# GSM.net
KiCad netlist of a schematic drawn in Altium Designer
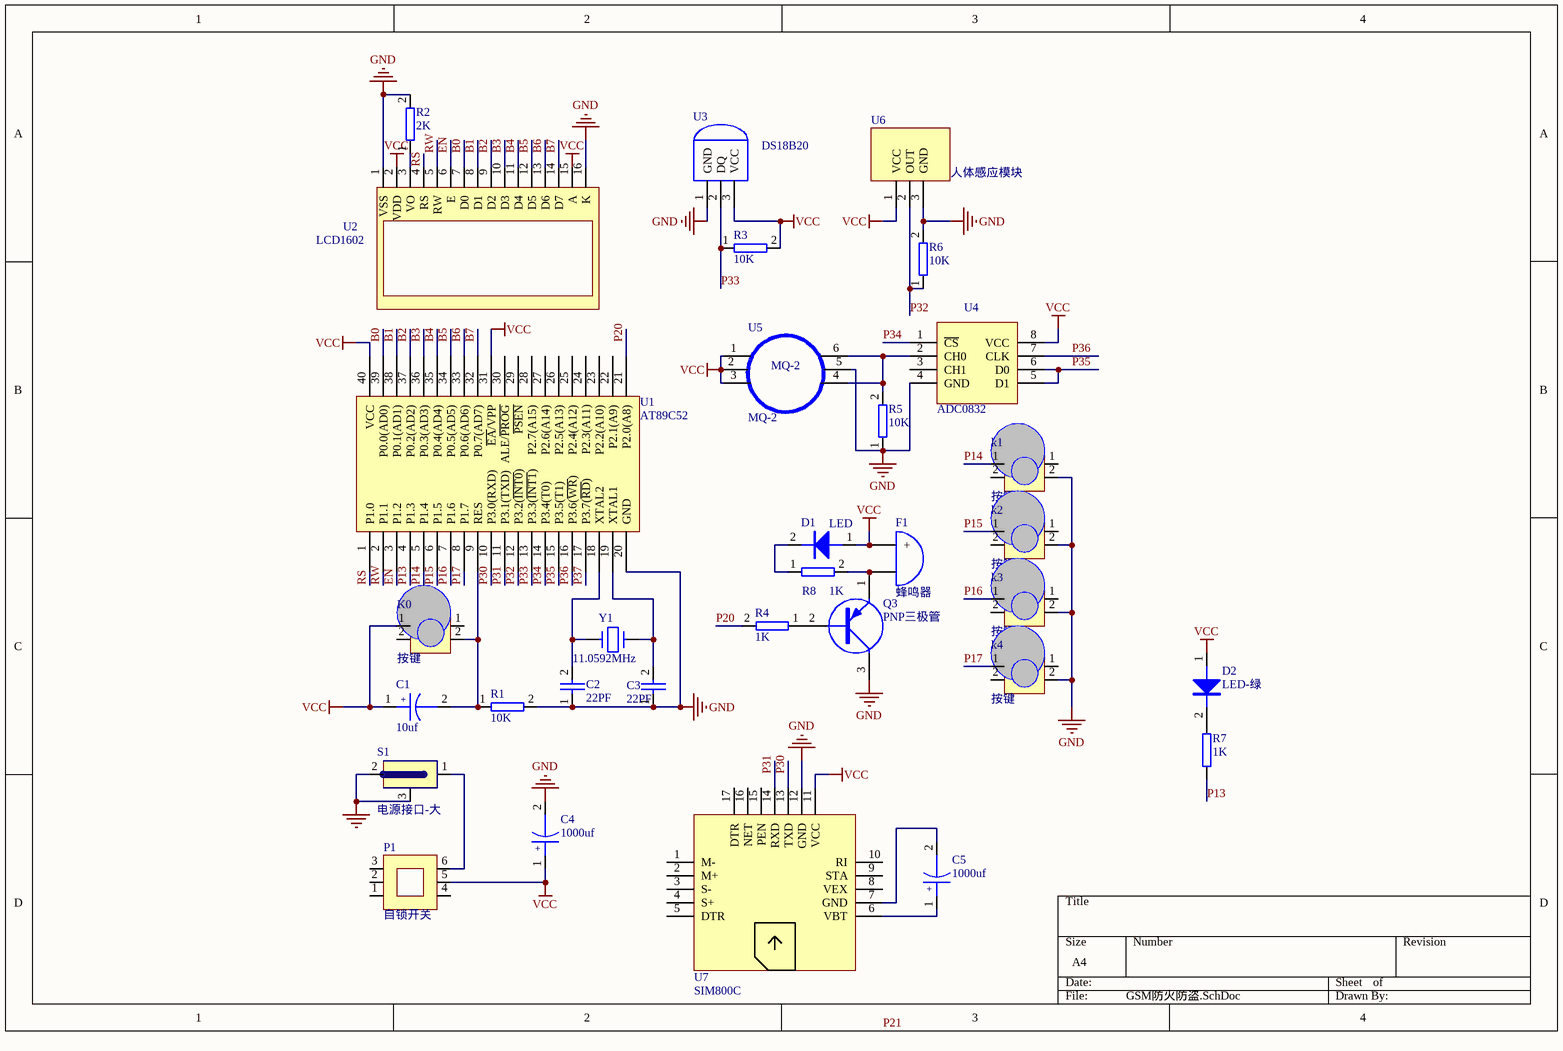
[diagram p0: GSM防火防盗.SchDoc]

(export (version "E")
  (design (tool "Eeschema 10.0.6"))
  (components
    (comp (ref "C1") (value "10uf") (footprint "电容-电解10UF") (libsource (lib "元件集成库") (part "电解电容")))
    (comp (ref "C2") (value "22PF") (footprint "电容-瓷片") (libsource (lib "元件集成库") (part "瓷片电容")))
    (comp (ref "C3") (value "22PF") (footprint "电容-瓷片") (libsource (lib "元件集成库") (part "瓷片电容")))
    (comp (ref "C4")
      (value "1000uf")
      (footprint "电容-电解1000UF - 25V")
      (libsource (lib "元件集成库") (part "电解电容-1000uf-25v"))
    )
    (comp (ref "C5")
      (value "1000uf")
      (footprint "电容-电解1000UF - 25V")
      (libsource (lib "元件集成库") (part "电解电容-1000uf-25v"))
    )
    (comp (ref "D1") (value "LED") (footprint "LED") (libsource (lib "元件集成库") (part "LED")))
    (comp (ref "D2") (value "LED-绿") (footprint "LED-5MM") (libsource (lib "元件集成库") (part "LED-5MM")))
    (comp (ref "F1") (value "蜂鸣器") (footprint "蜂鸣器") (libsource (lib "元件集成库") (part "蜂鸣器")))
    (comp (ref "K0") (value "按键") (footprint "按键") (libsource (lib "元件集成库") (part "按键")))
    (comp (ref "k1") (value "按键") (footprint "按键") (libsource (lib "元件集成库") (part "按键")))
    (comp (ref "k2") (value "按键") (footprint "按键") (libsource (lib "元件集成库") (part "按键")))
    (comp (ref "k3") (value "按键") (footprint "按键") (libsource (lib "元件集成库") (part "按键")))
    (comp (ref "k4") (value "按键") (footprint "按键") (libsource (lib "元件集成库") (part "按键")))
    (comp (ref "P1") (value "自锁开关") (footprint "自锁开关") (libsource (lib "元件集成库") (part "自锁开关")))
    (comp (ref "Q3") (value "PNP三极管") (footprint "三极管") (libsource (lib "元件集成库") (part "PNP三极管")))
    (comp (ref "R1") (value "10K") (footprint "电阻") (libsource (lib "元件集成库") (part "电阻-定值")))
    (comp (ref "R2") (value "2K") (footprint "电阻") (libsource (lib "元件集成库") (part "电阻-定值")))
    (comp (ref "R3") (value "10K") (footprint "电阻") (libsource (lib "元件集成库") (part "电阻-定值")))
    (comp (ref "R4") (value "1K") (footprint "电阻") (libsource (lib "元件集成库") (part "电阻-定值")))
    (comp (ref "R5") (value "10K") (footprint "电阻") (libsource (lib "元件集成库") (part "电阻-定值")))
    (comp (ref "R6") (value "10K") (footprint "电阻") (libsource (lib "元件集成库") (part "电阻-定值")))
    (comp (ref "R7") (value "1K") (footprint "电阻") (libsource (lib "") (part "电阻-定值_1")))
    (comp (ref "R8") (value "1K") (footprint "电阻") (libsource (lib "元件集成库") (part "电阻-定值")))
    (comp (ref "S1") (value "电源接口-大") (footprint "电源座-大") (libsource (lib "元件集成库") (part "电源接口-大")))
    (comp (ref "U1") (value "AT89C52") (footprint "底座40P") (libsource (lib "元件集成库") (part "STC89C52")))
    (comp (ref "U2") (value "LCD1602") (footprint "LCD1602") (libsource (lib "元件集成库") (part "LCD1602")))
    (comp (ref "U3") (value "DS18B20") (footprint "三极管") (libsource (lib "元件集成库") (part "DS18B20")))
    (comp (ref "U4") (value "ADC0832") (footprint "底座8P") (libsource (lib "元件集成库") (part "ADC0832")))
    (comp (ref "U5") (value "MQ-2") (footprint "MQ-2") (libsource (lib "元件集成库") (part "MQ-2")))
    (comp (ref "U6") (value "人体感应模块") (footprint "人体感应模块") (libsource (lib "元件集成库") (part "人体感应模块")))
    (comp (ref "U7") (value "SIM800C") (footprint "SIM800C") (libsource (lib "元件集成库") (part "SIM800C")))
    (comp (ref "Y1") (value "11.0592MHz") (footprint "晶振") (libsource (lib "元件集成库") (part "晶振")))
  )
  (nets
    (net (code "1") (name "/B0") (class "Default")
      (node (ref "U1") (pin "39") (pinfunction "P0.0(AD0)_39") (pintype "passive"))
      (node (ref "U2") (pin "7") (pinfunction "D0_7") (pintype "passive"))
    )
    (net (code "2") (name "/B1") (class "Default")
      (node (ref "U1") (pin "38") (pinfunction "P0.1(AD1)_38") (pintype "passive"))
      (node (ref "U2") (pin "8") (pinfunction "D1_8") (pintype "passive"))
    )
    (net (code "3") (name "/B2") (class "Default")
      (node (ref "U1") (pin "37") (pinfunction "P0.2(AD2)_37") (pintype "passive"))
      (node (ref "U2") (pin "9") (pinfunction "D2_9") (pintype "passive"))
    )
    (net (code "4") (name "/B3") (class "Default")
      (node (ref "U1") (pin "36") (pinfunction "P0.3(AD3)_36") (pintype "passive"))
      (node (ref "U2") (pin "10") (pinfunction "D3_10") (pintype "passive"))
    )
    (net (code "5") (name "/B4") (class "Default")
      (node (ref "U1") (pin "35") (pinfunction "P0.4(AD4)_35") (pintype "passive"))
      (node (ref "U2") (pin "11") (pinfunction "D4_11") (pintype "passive"))
    )
    (net (code "6") (name "/B5") (class "Default")
      (node (ref "U1") (pin "34") (pinfunction "P0.5(AD5)_34") (pintype "passive"))
      (node (ref "U2") (pin "12") (pinfunction "D5_12") (pintype "passive"))
    )
    (net (code "7") (name "/B6") (class "Default")
      (node (ref "U1") (pin "33") (pinfunction "P0.6(AD6)_33") (pintype "passive"))
      (node (ref "U2") (pin "13") (pinfunction "D6_13") (pintype "passive"))
    )
    (net (code "8") (name "/B7") (class "Default")
      (node (ref "U1") (pin "32") (pinfunction "P0.7(AD7)_32") (pintype "passive"))
      (node (ref "U2") (pin "14") (pinfunction "D7_14") (pintype "passive"))
    )
    (net (code "9") (name "/EN") (class "Default")
      (node (ref "U1") (pin "3") (pinfunction "P1.2_3") (pintype "passive"))
      (node (ref "U2") (pin "6") (pinfunction "E_6") (pintype "passive"))
    )
    (net (code "10") (name "/P13") (class "Default")
      (node (ref "R7") (pin "1") (pinfunction "1_1") (pintype "passive"))
      (node (ref "U1") (pin "4") (pinfunction "P1.3_4") (pintype "passive"))
    )
    (net (code "11") (name "/P14") (class "Default")
      (node (ref "U1") (pin "5") (pinfunction "P1.4_5") (pintype "passive"))
      (node (ref "k1") (pin "1") (pinfunction "1_1") (pintype "passive"))
    )
    (net (code "12") (name "/P15") (class "Default")
      (node (ref "U1") (pin "6") (pinfunction "P1.5_6") (pintype "passive"))
      (node (ref "k2") (pin "1") (pinfunction "1_1") (pintype "passive"))
    )
    (net (code "13") (name "/P16") (class "Default")
      (node (ref "U1") (pin "7") (pinfunction "P1.6_7") (pintype "passive"))
      (node (ref "k3") (pin "1") (pinfunction "1_1") (pintype "passive"))
    )
    (net (code "14") (name "/P17") (class "Default")
      (node (ref "U1") (pin "8") (pinfunction "P1.7_8") (pintype "passive"))
      (node (ref "k4") (pin "1") (pinfunction "1_1") (pintype "passive"))
    )
    (net (code "15") (name "/P20") (class "Default")
      (node (ref "R4") (pin "2") (pinfunction "2_2") (pintype "passive"))
      (node (ref "U1") (pin "21") (pinfunction "P2.0(A8)_21") (pintype "passive"))
    )
    (net (code "17") (name "/P30") (class "Default")
      (node (ref "U1") (pin "10") (pinfunction "P3.0(RXD)_10") (pintype "passive"))
      (node (ref "U7") (pin "13") (pinfunction "TXD_13") (pintype "passive"))
    )
    (net (code "18") (name "/P31") (class "Default")
      (node (ref "U1") (pin "11") (pinfunction "P3.1(TXD)_11") (pintype "passive"))
      (node (ref "U7") (pin "14") (pinfunction "RXD_14") (pintype "passive"))
    )
    (net (code "19") (name "/P32") (class "Default")
      (node (ref "R6") (pin "1") (pinfunction "1_1") (pintype "passive"))
      (node (ref "U1") (pin "12") (pinfunction "P3.2(~{INT0})_12") (pintype "passive"))
      (node (ref "U6") (pin "2") (pinfunction "OUT_2") (pintype "passive"))
    )
    (net (code "20") (name "/P33") (class "Default")
      (node (ref "R3") (pin "1") (pinfunction "1_1") (pintype "passive"))
      (node (ref "U1") (pin "13") (pinfunction "P3.3(~{INT1})_13") (pintype "passive"))
      (node (ref "U3") (pin "2") (pinfunction "DQ_2") (pintype "passive"))
    )
    (net (code "21") (name "/P34") (class "Default")
      (node (ref "U1") (pin "14") (pinfunction "P3.4(T0)_14") (pintype "passive"))
      (node (ref "U4") (pin "1") (pinfunction "~{CS}_1") (pintype "passive"))
    )
    (net (code "22") (name "/P35") (class "Default")
      (node (ref "U1") (pin "15") (pinfunction "P3.5(T1)_15") (pintype "passive"))
      (node (ref "U4") (pin "5") (pinfunction "D1_5") (pintype "passive"))
      (node (ref "U4") (pin "6") (pinfunction "D0_6") (pintype "passive"))
    )
    (net (code "23") (name "/P36") (class "Default")
      (node (ref "U1") (pin "16") (pinfunction "P3.6(~{WR})_16") (pintype "passive"))
      (node (ref "U4") (pin "7") (pinfunction "CLK_7") (pintype "passive"))
    )
    (net (code "24") (name "/P37") (class "Default")
      (node (ref "U1") (pin "17") (pinfunction "P3.7(~{RD})_17") (pintype "passive"))
    )
    (net (code "25") (name "/RS") (class "Default")
      (node (ref "U1") (pin "1") (pinfunction "P1.0_1") (pintype "passive"))
      (node (ref "U2") (pin "4") (pinfunction "RS_4") (pintype "passive"))
    )
    (net (code "26") (name "/RW") (class "Default")
      (node (ref "U1") (pin "2") (pinfunction "P1.1_2") (pintype "passive"))
      (node (ref "U2") (pin "5") (pinfunction "RW_5") (pintype "passive"))
    )
    (net (code "27") (name "GND") (class "Default")
      (node (ref "C2") (pin "1") (pinfunction "1_1") (pintype "passive"))
      (node (ref "C3") (pin "1") (pinfunction "1_1") (pintype "passive"))
      (node (ref "C4") (pin "2") (pinfunction "2_2") (pintype "passive"))
      (node (ref "Q3") (pin "3") (pinfunction "C_3") (pintype "passive"))
      (node (ref "R1") (pin "2") (pinfunction "2_2") (pintype "passive"))
      (node (ref "R2") (pin "2") (pinfunction "2_2") (pintype "passive"))
      (node (ref "R5") (pin "1") (pinfunction "1_1") (pintype "passive"))
      (node (ref "R6") (pin "2") (pinfunction "2_2") (pintype "passive"))
      (node (ref "S1") (pin "2") (pinfunction "2_2") (pintype "passive"))
      (node (ref "S1") (pin "3") (pinfunction "3_3") (pintype "passive"))
      (node (ref "U1") (pin "20") (pinfunction "GND_20") (pintype "passive"))
      (node (ref "U2") (pin "1") (pinfunction "VSS_1") (pintype "passive"))
      (node (ref "U2") (pin "16") (pinfunction "K_16") (pintype "passive"))
      (node (ref "U3") (pin "1") (pinfunction "GND_1") (pintype "passive"))
      (node (ref "U4") (pin "4") (pinfunction "GND_4") (pintype "passive"))
      (node (ref "U5") (pin "5") (pinfunction "5_5") (pintype "passive"))
      (node (ref "U6") (pin "3") (pinfunction "GND_3") (pintype "passive"))
      (node (ref "U7") (pin "12") (pinfunction "GND_12") (pintype "passive"))
      (node (ref "k1") (pin "2") (pinfunction "2_2") (pintype "passive"))
      (node (ref "k2") (pin "2") (pinfunction "2_2") (pintype "passive"))
      (node (ref "k3") (pin "2") (pinfunction "2_2") (pintype "passive"))
      (node (ref "k4") (pin "2") (pinfunction "2_2") (pintype "passive"))
    )
    (net (code "28") (name "Net-(C5-Pad2)") (class "Default")
      (node (ref "C5") (pin "2") (pinfunction "2_2") (pintype "passive"))
      (node (ref "U7") (pin "7") (pinfunction "GND_7") (pintype "passive"))
    )
    (net (code "29") (name "Net-(D1-Pad2)") (class "Default")
      (node (ref "D1") (pin "2") (pinfunction "2_2") (pintype "passive"))
      (node (ref "R8") (pin "1") (pinfunction "1_1") (pintype "passive"))
    )
    (net (code "30") (name "Net-(D2-Pad2)") (class "Default")
      (node (ref "D2") (pin "2") (pinfunction "2_2") (pintype "passive"))
      (node (ref "R7") (pin "2") (pinfunction "2_2") (pintype "passive"))
    )
    (net (code "31") (name "Net-(F1-B)") (class "Default")
      (node (ref "F1") (pin "2") (pinfunction "B_2") (pintype "passive"))
      (node (ref "Q3") (pin "1") (pinfunction "E_1") (pintype "passive"))
      (node (ref "R8") (pin "2") (pinfunction "2_2") (pintype "passive"))
    )
    (net (code "32") (name "Net-(P1-Pad6)") (class "Default")
      (node (ref "P1") (pin "6") (pinfunction "6_6") (pintype "passive"))
      (node (ref "S1") (pin "1") (pinfunction "1_1") (pintype "passive"))
    )
    (net (code "33") (name "Net-(Q3-B)") (class "Default")
      (node (ref "Q3") (pin "2") (pinfunction "B_2") (pintype "passive"))
      (node (ref "R4") (pin "1") (pinfunction "1_1") (pintype "passive"))
    )
    (net (code "34") (name "Net-(U1-RES)") (class "Default")
      (node (ref "C1") (pin "2") (pinfunction "2_2") (pintype "passive"))
      (node (ref "K0") (pin "2") (pinfunction "2_2") (pintype "passive"))
      (node (ref "R1") (pin "1") (pinfunction "1_1") (pintype "passive"))
      (node (ref "U1") (pin "9") (pinfunction "RES_9") (pintype "passive"))
    )
    (net (code "35") (name "Net-(U1-XTAL1)") (class "Default")
      (node (ref "C3") (pin "2") (pinfunction "2_2") (pintype "passive"))
      (node (ref "U1") (pin "19") (pinfunction "XTAL1_19") (pintype "passive"))
      (node (ref "Y1") (pin "2") (pinfunction "2_2") (pintype "passive"))
    )
    (net (code "36") (name "Net-(U1-XTAL2)") (class "Default")
      (node (ref "C2") (pin "2") (pinfunction "2_2") (pintype "passive"))
      (node (ref "U1") (pin "18") (pinfunction "XTAL2_18") (pintype "passive"))
      (node (ref "Y1") (pin "1") (pinfunction "1_1") (pintype "passive"))
    )
    (net (code "37") (name "Net-(U2-VO)") (class "Default")
      (node (ref "R2") (pin "1") (pinfunction "1_1") (pintype "passive"))
      (node (ref "U2") (pin "3") (pinfunction "VO_3") (pintype "passive"))
    )
    (net (code "38") (name "Net-(U4-CH0)") (class "Default")
      (node (ref "R5") (pin "2") (pinfunction "2_2") (pintype "passive"))
      (node (ref "U4") (pin "2") (pinfunction "CH0_2") (pintype "passive"))
      (node (ref "U5") (pin "4") (pinfunction "4_4") (pintype "passive"))
      (node (ref "U5") (pin "6") (pinfunction "6_6") (pintype "passive"))
    )
    (net (code "39") (name "Net-(U7-VBT)") (class "Default")
      (node (ref "C5") (pin "1") (pinfunction "1_1") (pintype "passive"))
      (node (ref "U7") (pin "6") (pinfunction "VBT_6") (pintype "passive"))
    )
    (net (code "40") (name "VCC") (class "Default")
      (node (ref "C1") (pin "1") (pinfunction "1_1") (pintype "passive"))
      (node (ref "C4") (pin "1") (pinfunction "1_1") (pintype "passive"))
      (node (ref "D1") (pin "1") (pinfunction "1_1") (pintype "passive"))
      (node (ref "D2") (pin "1") (pinfunction "1_1") (pintype "passive"))
      (node (ref "F1") (pin "1") (pinfunction "+_1") (pintype "passive"))
      (node (ref "K0") (pin "1") (pinfunction "1_1") (pintype "passive"))
      (node (ref "P1") (pin "5") (pinfunction "5_5") (pintype "passive"))
      (node (ref "R3") (pin "2") (pinfunction "2_2") (pintype "passive"))
      (node (ref "U1") (pin "31") (pinfunction "~{EA}/VPP_31") (pintype "passive"))
      (node (ref "U1") (pin "40") (pinfunction "VCC_40") (pintype "passive"))
      (node (ref "U2") (pin "15") (pinfunction "A_15") (pintype "passive"))
      (node (ref "U2") (pin "2") (pinfunction "VDD_2") (pintype "passive"))
      (node (ref "U3") (pin "3") (pinfunction "VCC_3") (pintype "passive"))
      (node (ref "U4") (pin "8") (pinfunction "VCC_8") (pintype "passive"))
      (node (ref "U5") (pin "1") (pinfunction "1_1") (pintype "passive"))
      (node (ref "U5") (pin "2") (pinfunction "2_2") (pintype "passive"))
      (node (ref "U5") (pin "3") (pinfunction "3_3") (pintype "passive"))
      (node (ref "U6") (pin "1") (pinfunction "VCC_1") (pintype "passive"))
      (node (ref "U7") (pin "11") (pinfunction "VCC_11") (pintype "passive"))
    )
    (net (code "41") (name "unconnected-(K0-Pad1)") (class "Default")
      (node (ref "K0") (pin "1") (pinfunction "1_1") (pintype "passive"))
    )
    (net (code "42") (name "unconnected-(K0-Pad2)") (class "Default")
      (node (ref "K0") (pin "2") (pinfunction "2_2") (pintype "passive"))
    )
    (net (code "43") (name "unconnected-(P1-Pad1)") (class "Default")
      (node (ref "P1") (pin "1") (pinfunction "1_1") (pintype "passive"))
    )
    (net (code "44") (name "unconnected-(P1-Pad2)") (class "Default")
      (node (ref "P1") (pin "2") (pinfunction "2_2") (pintype "passive"))
    )
    (net (code "45") (name "unconnected-(P1-Pad3)") (class "Default")
      (node (ref "P1") (pin "3") (pinfunction "3_3") (pintype "passive"))
    )
    (net (code "46") (name "unconnected-(P1-Pad4)") (class "Default")
      (node (ref "P1") (pin "4") (pinfunction "4_4") (pintype "passive"))
    )
    (net (code "47") (name "unconnected-(U1-ALE{slash}~{PROG}-Pad30)") (class "Default")
      (node (ref "U1") (pin "30") (pinfunction "ALE/~{PROG}_30") (pintype "passive"))
    )
    (net (code "48") (name "unconnected-(U1-P2.1(A9)-Pad22)") (class "Default")
      (node (ref "U1") (pin "22") (pinfunction "P2.1(A9)_22") (pintype "passive"))
    )
    (net (code "49") (name "unconnected-(U1-P2.2(A10)-Pad23)") (class "Default")
      (node (ref "U1") (pin "23") (pinfunction "P2.2(A10)_23") (pintype "passive"))
    )
    (net (code "50") (name "unconnected-(U1-P2.3(A11)-Pad24)") (class "Default")
      (node (ref "U1") (pin "24") (pinfunction "P2.3(A11)_24") (pintype "passive"))
    )
    (net (code "51") (name "unconnected-(U1-P2.4(A12)-Pad25)") (class "Default")
      (node (ref "U1") (pin "25") (pinfunction "P2.4(A12)_25") (pintype "passive"))
    )
    (net (code "52") (name "unconnected-(U1-P2.5(A13)-Pad26)") (class "Default")
      (node (ref "U1") (pin "26") (pinfunction "P2.5(A13)_26") (pintype "passive"))
    )
    (net (code "53") (name "unconnected-(U1-P2.6(A14)-Pad27)") (class "Default")
      (node (ref "U1") (pin "27") (pinfunction "P2.6(A14)_27") (pintype "passive"))
    )
    (net (code "54") (name "unconnected-(U1-P2.7(A15)-Pad28)") (class "Default")
      (node (ref "U1") (pin "28") (pinfunction "P2.7(A15)_28") (pintype "passive"))
    )
    (net (code "55") (name "unconnected-(U1-~{PSEN}-Pad29)") (class "Default")
      (node (ref "U1") (pin "29") (pinfunction "~{PSEN}_29") (pintype "passive"))
    )
    (net (code "56") (name "unconnected-(U4-CH1-Pad3)") (class "Default")
      (node (ref "U4") (pin "3") (pinfunction "CH1_3") (pintype "passive"))
    )
    (net (code "57") (name "unconnected-(U7-DTR-Pad5)") (class "Default")
      (node (ref "U7") (pin "5") (pinfunction "DTR_5") (pintype "passive"))
    )
    (net (code "58") (name "unconnected-(U7-DTR-Pad17)") (class "Default")
      (node (ref "U7") (pin "17") (pinfunction "DTR_17") (pintype "passive"))
    )
    (net (code "59") (name "unconnected-(U7-M+-Pad2)") (class "Default")
      (node (ref "U7") (pin "2") (pinfunction "M+_2") (pintype "passive"))
    )
    (net (code "60") (name "unconnected-(U7-M--Pad1)") (class "Default")
      (node (ref "U7") (pin "1") (pinfunction "M-_1") (pintype "passive"))
    )
    (net (code "61") (name "unconnected-(U7-NET-Pad16)") (class "Default")
      (node (ref "U7") (pin "16") (pinfunction "NET_16") (pintype "passive"))
    )
    (net (code "62") (name "unconnected-(U7-PEN-Pad15)") (class "Default")
      (node (ref "U7") (pin "15") (pinfunction "PEN_15") (pintype "passive"))
    )
    (net (code "63") (name "unconnected-(U7-RI-Pad10)") (class "Default")
      (node (ref "U7") (pin "10") (pinfunction "RI_10") (pintype "passive"))
    )
    (net (code "64") (name "unconnected-(U7-S+-Pad4)") (class "Default")
      (node (ref "U7") (pin "4") (pinfunction "S+_4") (pintype "passive"))
    )
    (net (code "65") (name "unconnected-(U7-S--Pad3)") (class "Default")
      (node (ref "U7") (pin "3") (pinfunction "S-_3") (pintype "passive"))
    )
    (net (code "66") (name "unconnected-(U7-STA-Pad9)") (class "Default")
      (node (ref "U7") (pin "9") (pinfunction "STA_9") (pintype "passive"))
    )
    (net (code "67") (name "unconnected-(U7-VEX-Pad8)") (class "Default")
      (node (ref "U7") (pin "8") (pinfunction "VEX_8") (pintype "passive"))
    )
    (net (code "68") (name "unconnected-(k1-Pad1)") (class "Default")
      (node (ref "k1") (pin "1") (pinfunction "1_1") (pintype "passive"))
    )
    (net (code "69") (name "unconnected-(k1-Pad2)") (class "Default")
      (node (ref "k1") (pin "2") (pinfunction "2_2") (pintype "passive"))
    )
    (net (code "70") (name "unconnected-(k2-Pad1)") (class "Default")
      (node (ref "k2") (pin "1") (pinfunction "1_1") (pintype "passive"))
    )
    (net (code "71") (name "unconnected-(k2-Pad2)") (class "Default")
      (node (ref "k2") (pin "2") (pinfunction "2_2") (pintype "passive"))
    )
    (net (code "72") (name "unconnected-(k3-Pad1)") (class "Default")
      (node (ref "k3") (pin "1") (pinfunction "1_1") (pintype "passive"))
    )
    (net (code "73") (name "unconnected-(k3-Pad2)") (class "Default")
      (node (ref "k3") (pin "2") (pinfunction "2_2") (pintype "passive"))
    )
    (net (code "74") (name "unconnected-(k4-Pad1)") (class "Default")
      (node (ref "k4") (pin "1") (pinfunction "1_1") (pintype "passive"))
    )
    (net (code "75") (name "unconnected-(k4-Pad2)") (class "Default")
      (node (ref "k4") (pin "2") (pinfunction "2_2") (pintype "passive"))
    )
  )
)
